# breakout_mdbt40.net
KiCad netlist of a schematic drawn in EAGLE
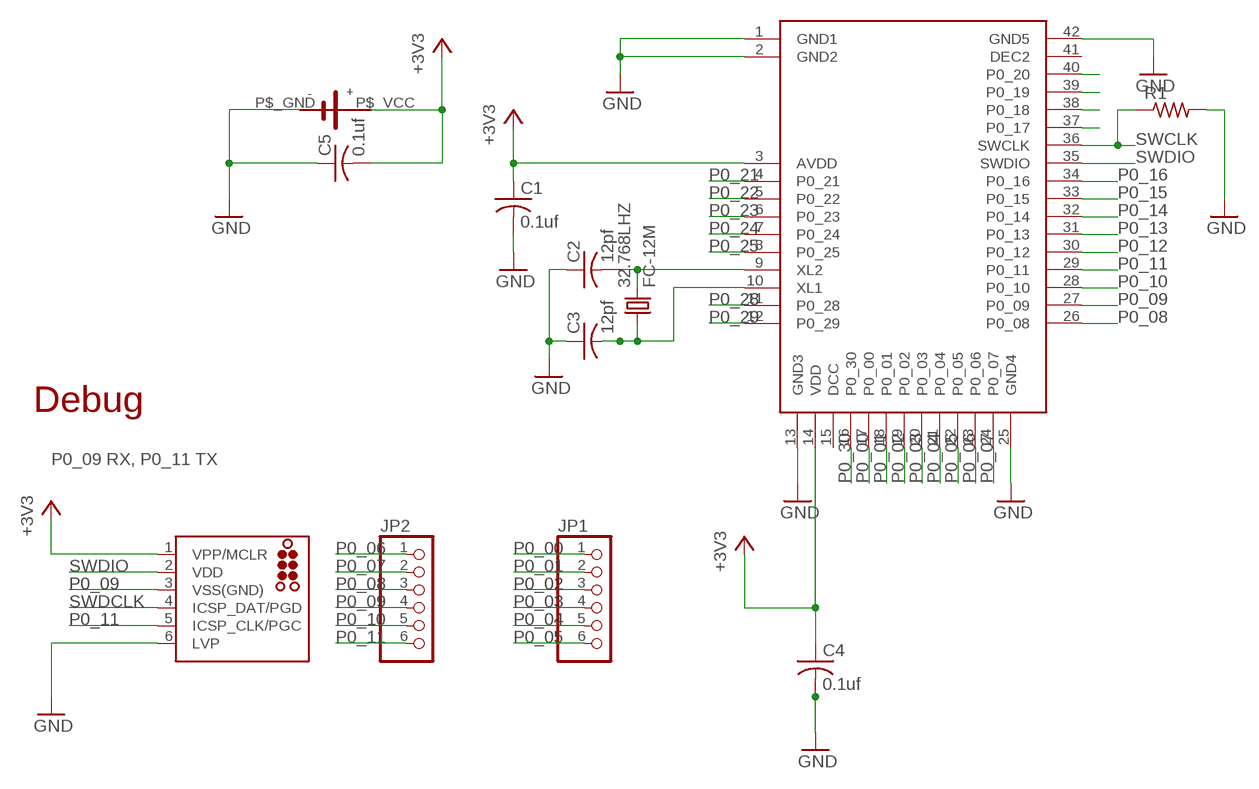
[diagram p0: schematic, sheet 1]

(export (version "E")
  (design (tool "Eeschema 10.0.6"))
  (components
    (comp (ref "32.768LHZ")
      (value "FC-12M")
      (footprint "eagle-import:FC-12M")
      (libsource (lib "eagle-import") (part "FC-12M"))
    )
    (comp (ref "C1")
      (value "0.1uf")
      (footprint "eagle-import:C0603")
      (libsource (lib "eagle-import") (part "C-USC0603"))
    )
    (comp (ref "C2")
      (value "12pf")
      (footprint "eagle-import:C0603")
      (libsource (lib "eagle-import") (part "C-USC0603"))
    )
    (comp (ref "C3")
      (value "12pf")
      (footprint "eagle-import:C0603")
      (libsource (lib "eagle-import") (part "C-USC0603"))
    )
    (comp (ref "C4")
      (value "0.1uf")
      (footprint "eagle-import:C0603")
      (libsource (lib "eagle-import") (part "C-USC0603"))
    )
    (comp (ref "C5")
      (value "0.1uf")
      (footprint "eagle-import:C0603")
      (libsource (lib "eagle-import") (part "C-USC0603"))
    )
    (comp (ref "J2")
      (value "TC2030-MCP")
      (footprint "eagle-import:TC2030-MCP")
      (libsource (lib "eagle-import") (part "TC2030-MCP"))
    )
    (comp (ref "JP1")
      (value "PINHD-1X6")
      (footprint "eagle-import:1X06")
      (libsource (lib "eagle-import") (part "PINHD-1X6"))
    )
    (comp (ref "JP2")
      (value "PINHD-1X6")
      (footprint "eagle-import:1X06")
      (libsource (lib "eagle-import") (part "PINHD-1X6"))
    )
    (comp (ref "R1")
      (value "R-US_R0603")
      (footprint "eagle-import:R0603")
      (libsource (lib "eagle-import") (part "R-US_R0603"))
    )
    (comp (ref "U$1")
      (value "RAYTAC-MDBT40")
      (footprint "eagle-import:RAYTAC-MDBT40")
      (libsource (lib "eagle-import") (part "RAYTAC-MDBT40"))
    )
    (comp (ref "U$3")
      (value "SMTU2450-BOTTOM-MINI")
      (footprint "eagle-import:SMTU2450-BOTTOM-MINI")
      (libsource (lib "eagle-import") (part "SMTU2450-BOTTOM-MINI"))
    )
  )
  (nets
    (net (code "1") (name "+3V3") (class "Default")
      (node (ref "C1") (pin "1") (pinfunction "1_1") (pintype "passive"))
      (node (ref "C4") (pin "1") (pinfunction "1_1") (pintype "passive"))
      (node (ref "C5") (pin "2") (pinfunction "2_2") (pintype "passive"))
      (node (ref "J2") (pin "1") (pinfunction "VPP/MCLR_1") (pintype "passive"))
      (node (ref "U$1") (pin "14") (pinfunction "VDD_14") (pintype "bidirectional"))
      (node (ref "U$1") (pin "3") (pinfunction "AVDD_3") (pintype "bidirectional"))
      (node (ref "U$3") (pin "P$_VCC") (pinfunction "P$_VCC_P$_VCC") (pintype "bidirectional"))
    )
    (net (code "2") (name "/P0_00") (class "Default")
      (node (ref "JP1") (pin "1") (pinfunction "1_1") (pintype "passive"))
      (node (ref "U$1") (pin "17") (pinfunction "P0_00_17") (pintype "bidirectional"))
    )
    (net (code "3") (name "/P0_01") (class "Default")
      (node (ref "JP1") (pin "2") (pinfunction "2_2") (pintype "passive"))
      (node (ref "U$1") (pin "18") (pinfunction "P0_01_18") (pintype "bidirectional"))
    )
    (net (code "4") (name "/P0_02") (class "Default")
      (node (ref "JP1") (pin "3") (pinfunction "3_3") (pintype "passive"))
      (node (ref "U$1") (pin "19") (pinfunction "P0_02_19") (pintype "bidirectional"))
    )
    (net (code "5") (name "/P0_03") (class "Default")
      (node (ref "JP1") (pin "4") (pinfunction "4_4") (pintype "passive"))
      (node (ref "U$1") (pin "20") (pinfunction "P0_03_20") (pintype "bidirectional"))
    )
    (net (code "6") (name "/P0_04") (class "Default")
      (node (ref "JP1") (pin "5") (pinfunction "5_5") (pintype "passive"))
      (node (ref "U$1") (pin "21") (pinfunction "P0_04_21") (pintype "bidirectional"))
    )
    (net (code "7") (name "/P0_05") (class "Default")
      (node (ref "JP1") (pin "6") (pinfunction "6_6") (pintype "passive"))
      (node (ref "U$1") (pin "22") (pinfunction "P0_05_22") (pintype "bidirectional"))
    )
    (net (code "8") (name "/P0_06") (class "Default")
      (node (ref "JP2") (pin "1") (pinfunction "1_1") (pintype "passive"))
      (node (ref "U$1") (pin "23") (pinfunction "P0_06_23") (pintype "bidirectional"))
    )
    (net (code "9") (name "/P0_07") (class "Default")
      (node (ref "JP2") (pin "2") (pinfunction "2_2") (pintype "passive"))
      (node (ref "U$1") (pin "24") (pinfunction "P0_07_24") (pintype "bidirectional"))
    )
    (net (code "10") (name "/P0_08") (class "Default")
      (node (ref "JP2") (pin "3") (pinfunction "3_3") (pintype "passive"))
      (node (ref "U$1") (pin "26") (pinfunction "P0_08_26") (pintype "bidirectional"))
    )
    (net (code "11") (name "/P0_09") (class "Default")
      (node (ref "J2") (pin "3") (pinfunction "VSS(GND)_3") (pintype "power_in"))
      (node (ref "JP2") (pin "4") (pinfunction "4_4") (pintype "passive"))
      (node (ref "U$1") (pin "27") (pinfunction "P0_09_27") (pintype "bidirectional"))
    )
    (net (code "12") (name "/P0_10") (class "Default")
      (node (ref "JP2") (pin "5") (pinfunction "5_5") (pintype "passive"))
      (node (ref "U$1") (pin "28") (pinfunction "P0_10_28") (pintype "bidirectional"))
    )
    (net (code "13") (name "/P0_11") (class "Default")
      (node (ref "J2") (pin "5") (pinfunction "ICSP_CLK/PGC_5") (pintype "output"))
      (node (ref "JP2") (pin "6") (pinfunction "6_6") (pintype "passive"))
      (node (ref "U$1") (pin "29") (pinfunction "P0_11_29") (pintype "bidirectional"))
    )
    (net (code "14") (name "/P0_12") (class "Default")
      (node (ref "U$1") (pin "30") (pinfunction "P0_12_30") (pintype "bidirectional"))
    )
    (net (code "15") (name "/P0_13") (class "Default")
      (node (ref "U$1") (pin "31") (pinfunction "P0_13_31") (pintype "bidirectional"))
    )
    (net (code "16") (name "/P0_14") (class "Default")
      (node (ref "U$1") (pin "32") (pinfunction "P0_14_32") (pintype "bidirectional"))
    )
    (net (code "17") (name "/P0_15") (class "Default")
      (node (ref "U$1") (pin "33") (pinfunction "P0_15_33") (pintype "bidirectional"))
    )
    (net (code "18") (name "/P0_16") (class "Default")
      (node (ref "U$1") (pin "34") (pinfunction "P0_16_34") (pintype "bidirectional"))
    )
    (net (code "19") (name "/P0_21") (class "Default")
      (node (ref "U$1") (pin "4") (pinfunction "P0_21_4") (pintype "bidirectional"))
    )
    (net (code "20") (name "/P0_22") (class "Default")
      (node (ref "U$1") (pin "5") (pinfunction "P0_22_5") (pintype "bidirectional"))
    )
    (net (code "21") (name "/P0_23") (class "Default")
      (node (ref "U$1") (pin "6") (pinfunction "P0_23_6") (pintype "bidirectional"))
    )
    (net (code "22") (name "/P0_24") (class "Default")
      (node (ref "U$1") (pin "7") (pinfunction "P0_24_7") (pintype "bidirectional"))
    )
    (net (code "23") (name "/P0_25") (class "Default")
      (node (ref "U$1") (pin "8") (pinfunction "P0_25_8") (pintype "bidirectional"))
    )
    (net (code "24") (name "/P0_28") (class "Default")
      (node (ref "U$1") (pin "11") (pinfunction "P0_28_11") (pintype "bidirectional"))
    )
    (net (code "25") (name "/P0_29") (class "Default")
      (node (ref "U$1") (pin "12") (pinfunction "P0_29_12") (pintype "bidirectional"))
    )
    (net (code "26") (name "/P0_30") (class "Default")
      (node (ref "U$1") (pin "16") (pinfunction "P0_30_16") (pintype "bidirectional"))
    )
    (net (code "27") (name "/SWCLK") (class "Default")
      (node (ref "R1") (pin "1") (pinfunction "1_1") (pintype "passive"))
      (node (ref "U$1") (pin "36") (pinfunction "SWCLK_36") (pintype "bidirectional"))
    )
    (net (code "28") (name "/SWDCLK") (class "Default")
      (node (ref "J2") (pin "4") (pinfunction "ICSP_DAT/PGD_4") (pintype "bidirectional"))
    )
    (net (code "29") (name "/SWDIO") (class "Default")
      (node (ref "J2") (pin "2") (pinfunction "VDD_2") (pintype "power_in"))
      (node (ref "U$1") (pin "35") (pinfunction "SWDIO_35") (pintype "bidirectional"))
    )
    (net (code "30") (name "GND") (class "Default")
      (node (ref "C1") (pin "2") (pinfunction "2_2") (pintype "passive"))
      (node (ref "C2") (pin "1") (pinfunction "1_1") (pintype "passive"))
      (node (ref "C3") (pin "1") (pinfunction "1_1") (pintype "passive"))
      (node (ref "C4") (pin "2") (pinfunction "2_2") (pintype "passive"))
      (node (ref "C5") (pin "1") (pinfunction "1_1") (pintype "passive"))
      (node (ref "J2") (pin "6") (pinfunction "LVP_6") (pintype "bidirectional"))
      (node (ref "R1") (pin "2") (pinfunction "2_2") (pintype "passive"))
      (node (ref "U$1") (pin "1") (pinfunction "GND1_1") (pintype "bidirectional"))
      (node (ref "U$1") (pin "13") (pinfunction "GND3_13") (pintype "bidirectional"))
      (node (ref "U$1") (pin "2") (pinfunction "GND2_2") (pintype "bidirectional"))
      (node (ref "U$1") (pin "25") (pinfunction "GND4_25") (pintype "bidirectional"))
      (node (ref "U$1") (pin "42") (pinfunction "GND5_42") (pintype "bidirectional"))
      (node (ref "U$3") (pin "P$_GND") (pinfunction "P$_GND_P$_GND") (pintype "bidirectional"))
    )
    (net (code "31") (name "Net-(U$1-XL1)") (class "Default")
      (node (ref "32.768LHZ") (pin "1") (pinfunction "1_1") (pintype "passive"))
      (node (ref "C3") (pin "2") (pinfunction "2_2") (pintype "passive"))
      (node (ref "U$1") (pin "10") (pinfunction "XL1_10") (pintype "bidirectional"))
    )
    (net (code "32") (name "Net-(U$1-XL2)") (class "Default")
      (node (ref "32.768LHZ") (pin "2") (pinfunction "2_2") (pintype "passive"))
      (node (ref "C2") (pin "2") (pinfunction "2_2") (pintype "passive"))
      (node (ref "U$1") (pin "9") (pinfunction "XL2_9") (pintype "bidirectional"))
    )
    (net (code "33") (name "unconnected-(U$1-DCC-Pad15)") (class "Default")
      (node (ref "U$1") (pin "15") (pinfunction "DCC_15") (pintype "bidirectional"))
    )
    (net (code "34") (name "unconnected-(U$1-DEC2-Pad41)") (class "Default")
      (node (ref "U$1") (pin "41") (pinfunction "DEC2_41") (pintype "bidirectional"))
    )
    (net (code "35") (name "unconnected-(U$1-P0_17-Pad37)") (class "Default")
      (node (ref "U$1") (pin "37") (pinfunction "P0_17_37") (pintype "bidirectional"))
    )
    (net (code "36") (name "unconnected-(U$1-P0_18-Pad38)") (class "Default")
      (node (ref "U$1") (pin "38") (pinfunction "P0_18_38") (pintype "bidirectional"))
    )
    (net (code "37") (name "unconnected-(U$1-P0_19-Pad39)") (class "Default")
      (node (ref "U$1") (pin "39") (pinfunction "P0_19_39") (pintype "bidirectional"))
    )
    (net (code "38") (name "unconnected-(U$1-P0_20-Pad40)") (class "Default")
      (node (ref "U$1") (pin "40") (pinfunction "P0_20_40") (pintype "bidirectional"))
    )
  )
)
